# mLampMine.net
KiCad netlist of a schematic drawn in EAGLE
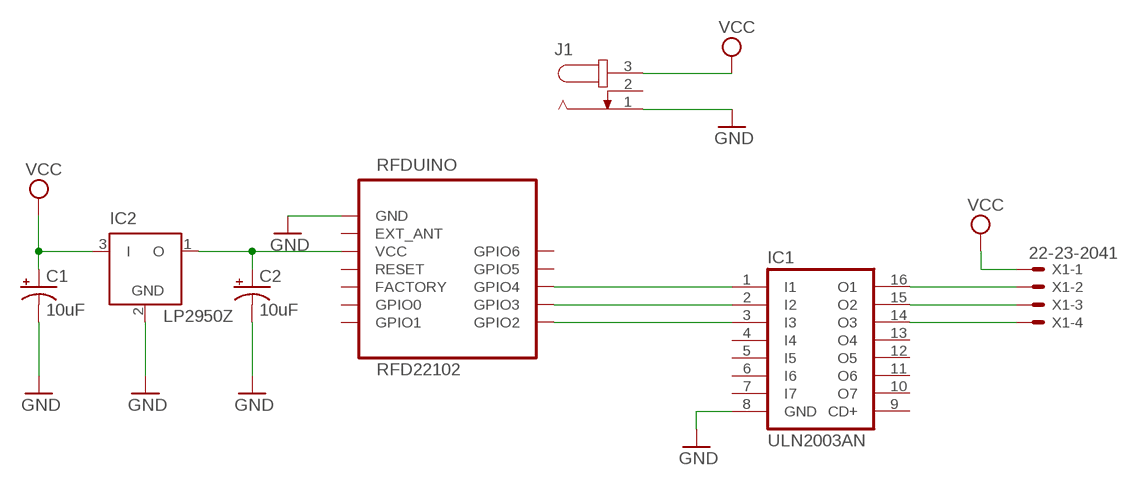
[diagram p0: schematic, sheet 1]

(export (version "E")
  (design (tool "Eeschema 10.0.6"))
  (components
    (comp (ref "C1")
      (value "10uF")
      (footprint "eagle-import:CPOL-RADIAL-10UF-25V")
      (libsource (lib "eagle-import") (part "CAP_POLPTH2"))
    )
    (comp (ref "C2")
      (value "10uF")
      (footprint "eagle-import:CPOL-RADIAL-10UF-25V")
      (libsource (lib "eagle-import") (part "CAP_POLPTH2"))
    )
    (comp (ref "IC1")
      (value "ULN2003AN")
      (footprint "eagle-import:DIL16")
      (libsource (lib "eagle-import") (part "ULN2003AN"))
    )
    (comp (ref "IC2")
      (value "LP2950Z")
      (footprint "eagle-import:TO92")
      (libsource (lib "eagle-import") (part "LP2950Z"))
    )
    (comp (ref "J1")
      (value "JACK-PLUG0")
      (footprint "eagle-import:SPC4077")
      (libsource (lib "eagle-import") (part "JACK-PLUG0"))
    )
    (comp (ref "RFDUINO")
      (value "RFD22102")
      (footprint "eagle-import:RFD22102")
      (libsource (lib "eagle-import") (part "RFD22102"))
    )
    (comp (ref "X1")
      (value "22-23-2041")
      (footprint "eagle-import:22-23-2041")
      (fields (field (name "MF") "MOLEX"))
      (libsource (lib "eagle-import") (part "22-23-2041"))
    )
  )
  (nets
    (net (code "1") (name "GND") (class "Default")
      (node (ref "C1") (pin "2") (pinfunction "-_2") (pintype "passive"))
      (node (ref "C2") (pin "2") (pinfunction "-_2") (pintype "passive"))
      (node (ref "IC1") (pin "8") (pinfunction "GND_8") (pintype "power_in"))
      (node (ref "IC2") (pin "2") (pinfunction "GND_2") (pintype "power_in"))
      (node (ref "J1") (pin "1") (pinfunction "1_1") (pintype "passive"))
      (node (ref "RFDUINO") (pin "GND") (pinfunction "GND_GND") (pintype "power_in"))
    )
    (net (code "2") (name "Net-(C2-+)") (class "Default")
      (node (ref "C2") (pin "1") (pinfunction "+_1") (pintype "passive"))
      (node (ref "IC2") (pin "1") (pinfunction "O_1") (pintype "input"))
      (node (ref "RFDUINO") (pin "VCC") (pinfunction "VCC_VCC") (pintype "power_in"))
    )
    (net (code "3") (name "Net-(IC1-I1)") (class "Default")
      (node (ref "IC1") (pin "1") (pinfunction "I1_1") (pintype "input"))
      (node (ref "RFDUINO") (pin "GPIO4") (pinfunction "GPIO4_GPIO4") (pintype "bidirectional"))
    )
    (net (code "4") (name "Net-(IC1-I2)") (class "Default")
      (node (ref "IC1") (pin "2") (pinfunction "I2_2") (pintype "input"))
      (node (ref "RFDUINO") (pin "GPIO3") (pinfunction "GPIO3_GPIO3") (pintype "bidirectional"))
    )
    (net (code "5") (name "Net-(IC1-I3)") (class "Default")
      (node (ref "IC1") (pin "3") (pinfunction "I3_3") (pintype "input"))
      (node (ref "RFDUINO") (pin "GPIO2") (pinfunction "GPIO2_GPIO2") (pintype "bidirectional"))
    )
    (net (code "6") (name "Net-(IC1-O1)") (class "Default")
      (node (ref "IC1") (pin "16") (pinfunction "O1_16") (pintype "open_collector"))
      (node (ref "X1") (pin "2") (pinfunction "S_2") (pintype "passive"))
    )
    (net (code "7") (name "Net-(IC1-O2)") (class "Default")
      (node (ref "IC1") (pin "15") (pinfunction "O2_15") (pintype "open_collector"))
      (node (ref "X1") (pin "3") (pinfunction "S_3") (pintype "passive"))
    )
    (net (code "8") (name "Net-(IC1-O3)") (class "Default")
      (node (ref "IC1") (pin "14") (pinfunction "O3_14") (pintype "open_collector"))
      (node (ref "X1") (pin "4") (pinfunction "S_4") (pintype "passive"))
    )
    (net (code "9") (name "VCC") (class "Default")
      (node (ref "C1") (pin "1") (pinfunction "+_1") (pintype "passive"))
      (node (ref "IC2") (pin "3") (pinfunction "I_3") (pintype "input"))
      (node (ref "J1") (pin "3") (pinfunction "3_3") (pintype "passive"))
      (node (ref "X1") (pin "1") (pinfunction "S_1") (pintype "passive"))
    )
    (net (code "10") (name "unconnected-(IC1-CD+-Pad9)") (class "Default")
      (node (ref "IC1") (pin "9") (pinfunction "CD+_9") (pintype "passive"))
    )
    (net (code "11") (name "unconnected-(IC1-I4-Pad4)") (class "Default")
      (node (ref "IC1") (pin "4") (pinfunction "I4_4") (pintype "input"))
    )
    (net (code "12") (name "unconnected-(IC1-I5-Pad5)") (class "Default")
      (node (ref "IC1") (pin "5") (pinfunction "I5_5") (pintype "input"))
    )
    (net (code "13") (name "unconnected-(IC1-I6-Pad6)") (class "Default")
      (node (ref "IC1") (pin "6") (pinfunction "I6_6") (pintype "input"))
    )
    (net (code "14") (name "unconnected-(IC1-I7-Pad7)") (class "Default")
      (node (ref "IC1") (pin "7") (pinfunction "I7_7") (pintype "input"))
    )
    (net (code "15") (name "unconnected-(IC1-O4-Pad13)") (class "Default")
      (node (ref "IC1") (pin "13") (pinfunction "O4_13") (pintype "open_collector"))
    )
    (net (code "16") (name "unconnected-(IC1-O5-Pad12)") (class "Default")
      (node (ref "IC1") (pin "12") (pinfunction "O5_12") (pintype "open_collector"))
    )
    (net (code "17") (name "unconnected-(IC1-O6-Pad11)") (class "Default")
      (node (ref "IC1") (pin "11") (pinfunction "O6_11") (pintype "open_collector"))
    )
    (net (code "18") (name "unconnected-(IC1-O7-Pad10)") (class "Default")
      (node (ref "IC1") (pin "10") (pinfunction "O7_10") (pintype "open_collector"))
    )
    (net (code "19") (name "unconnected-(J1-Pad2)") (class "Default")
      (node (ref "J1") (pin "2") (pinfunction "2_2") (pintype "passive"))
    )
    (net (code "20") (name "unconnected-(RFDUINO-PadEXT_ANT)") (class "Default")
      (node (ref "RFDUINO") (pin "EXT_ANT") (pinfunction "EXT_ANT_EXT_ANT") (pintype "no_connect"))
    )
    (net (code "21") (name "unconnected-(RFDUINO-PadFACTORY)") (class "Default")
      (node (ref "RFDUINO") (pin "FACTORY") (pinfunction "FACTORY_FACTORY") (pintype "bidirectional"))
    )
    (net (code "22") (name "unconnected-(RFDUINO-PadGPIO0)") (class "Default")
      (node (ref "RFDUINO") (pin "GPIO0") (pinfunction "GPIO0_GPIO0") (pintype "bidirectional"))
    )
    (net (code "23") (name "unconnected-(RFDUINO-PadGPIO1)") (class "Default")
      (node (ref "RFDUINO") (pin "GPIO1") (pinfunction "GPIO1_GPIO1") (pintype "bidirectional"))
    )
    (net (code "24") (name "unconnected-(RFDUINO-PadGPIO5)") (class "Default")
      (node (ref "RFDUINO") (pin "GPIO5") (pinfunction "GPIO5_GPIO5") (pintype "bidirectional"))
    )
    (net (code "25") (name "unconnected-(RFDUINO-PadGPIO6)") (class "Default")
      (node (ref "RFDUINO") (pin "GPIO6") (pinfunction "GPIO6_GPIO6") (pintype "bidirectional"))
    )
    (net (code "26") (name "unconnected-(RFDUINO-PadRESET)") (class "Default")
      (node (ref "RFDUINO") (pin "RESET") (pinfunction "RESET_RESET") (pintype "bidirectional"))
    )
  )
)
